# SPItoLVDS.net
KiCad netlist of a schematic drawn in Altium Designer
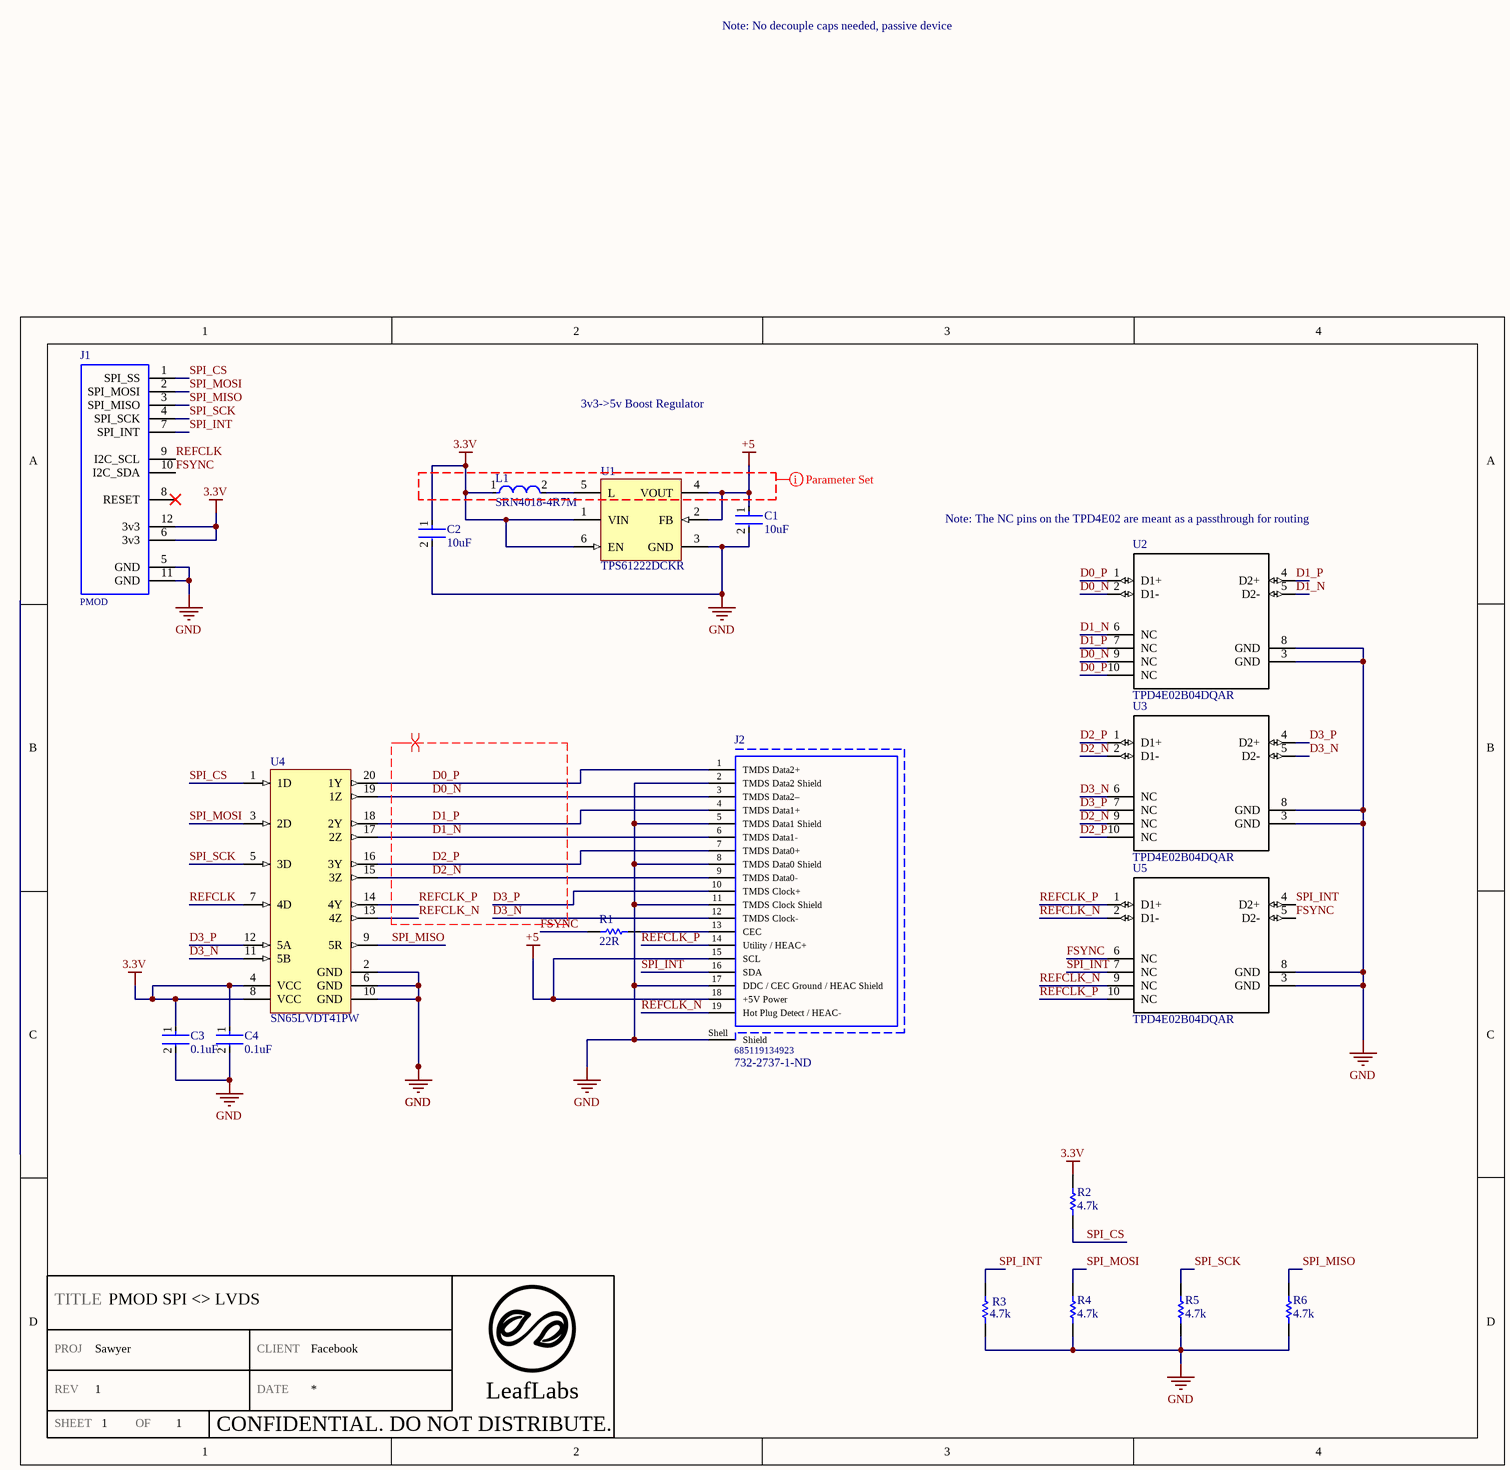
[diagram p0: SPItoLVDS.SchDoc]

(export (version "E")
  (design (tool "Eeschema 10.0.6"))
  (components
    (comp (ref "C1")
      (value "10uF")
      (footprint "FP-CC0603-DA-IPC_B")
      (description "CAP CER 10UF 0603")
      (libsource (lib "LeafLabs_Commercial") (part "CAP-0603-10uF"))
    )
    (comp (ref "C2")
      (value "10uF")
      (footprint "FP-CC0603-DA-IPC_B")
      (description "CAP CER 10UF 0603")
      (libsource (lib "LeafLabs_Commercial") (part "CAP-0603-10uF"))
    )
    (comp (ref "C3")
      (value "0.1uF")
      (footprint "FP-CC0603-DA-IPC_B")
      (description "CAP CER 0.1UF 16V X7R 0603")
      (fields
        (field (name "OCTOPART") "https://octopart.com/cc0603krx7r7bb104-yageo-192941")
        (field (name "TOLERANCE") "0.1")
      )
      (libsource (lib "LeafLabs_Commercial") (part "CAP-0603-0.1UF"))
    )
    (comp (ref "C4")
      (value "0.1uF")
      (footprint "FP-CC0603-DA-IPC_B")
      (description "CAP CER 0.1UF 16V X7R 0603")
      (fields
        (field (name "OCTOPART") "https://octopart.com/cc0603krx7r7bb104-yageo-192941")
        (field (name "TOLERANCE") "0.1")
      )
      (libsource (lib "LeafLabs_Commercial") (part "CAP-0603-0.1UF"))
    )
    (comp (ref "J1")
      (value "PMOD")
      (footprint "PMOD")
      (description "PMOD Connector, Through Hole, Standard pinout")
      (fields (field (name "PUBLISHER") "WurthElektronik"))
      (libsource (lib "LeafLabs_Commercial") (part "PMOD-TH"))
    )
    (comp (ref "J2")
      (value "685119134923")
      (footprint "685119134923")
      (description "HDMI Type A Receptacle WR-HDMI, Horizontal, SMT")
      (fields
        (field (name "MANUFACTURER") "Wurth Elektronik")
        (field (name "SUPPLIER PART NUMBER 1") "732-2737-1-ND")
        (field (name "PUBLISHER") "WurthElektronik")
      )
      (libsource (lib "LeafLabs_Commercial") (part "685119134923"))
    )
    (comp (ref "L1")
      (value "SRN4018-4R7M")
      (footprint "FP-SRN4018-MFG")
      (description "FIXED IND 4.7UH 1.9A 84 MOHM SMD")
      (fields
        (field (name "OCTOPART") "https://octopart.com/srn4018-4r7m-bourns-25452396")
        (field (name "TOLERANCE") "20%")
      )
      (libsource (lib "LeafLabs_Commercial") (part "SRN4018-4R7M"))
    )
    (comp (ref "R1")
      (value "22R")
      (footprint "RESC1609X50X30NL10T20")
      (description "Resistor 0603 22 Ohm")
      (libsource (lib "Resistors") (part "RES-0603-22R"))
    )
    (comp (ref "R2")
      (value "4.7k")
      (footprint "RESC1609X50X30NL10T20")
      (description "Resistor 0603 4.7k Ohm")
      (libsource (lib "LeafLabs_Commercial") (part "RES-0603-4.7k"))
    )
    (comp (ref "R3")
      (value "4.7k")
      (footprint "RESC1609X50X30NL10T20")
      (description "Resistor 0603 4.7k Ohm")
      (libsource (lib "LeafLabs_Commercial") (part "RES-0603-4.7k"))
    )
    (comp (ref "R4")
      (value "4.7k")
      (footprint "RESC1609X50X30NL10T20")
      (description "Resistor 0603 4.7k Ohm")
      (libsource (lib "LeafLabs_Commercial") (part "RES-0603-4.7k"))
    )
    (comp (ref "R5")
      (value "4.7k")
      (footprint "RESC1609X50X30NL10T20")
      (description "Resistor 0603 4.7k Ohm")
      (libsource (lib "LeafLabs_Commercial") (part "RES-0603-4.7k"))
    )
    (comp (ref "R6")
      (value "4.7k")
      (footprint "RESC1609X50X30NL10T20")
      (description "Resistor 0603 4.7k Ohm")
      (libsource (lib "LeafLabs_Commercial") (part "RES-0603-4.7k"))
    )
    (comp (ref "U1")
      (value "TPS61222DCKR")
      (footprint "SOT363_L")
      (fields (field (name "MANUFACTURER") "Texas Instruments"))
      (libsource (lib "LeafLabs_Commercial") (part "TPS61222DCKR"))
    )
    (comp (ref "U2")
      (value "TPD4E02B04DQAR")
      (footprint "DQA0010A")
      (description "4 Channel TVS Avalanch diode for USB3/HDMI2.0 protection")
      (fields
        (field (name "MANUFACTURER") "Texas Instruments")
        (field (name "COPYRIGHT") "Copyright (C) 2018 Accelerated Designs. All rights reserved")
      )
      (libsource (lib "LeafLabs_Commercial") (part "TPD4E02B04DQAR"))
    )
    (comp (ref "U3")
      (value "TPD4E02B04DQAR")
      (footprint "DQA0010A")
      (description "4 Channel TVS Avalanch diode for USB3/HDMI2.0 protection")
      (fields
        (field (name "MANUFACTURER") "Texas Instruments")
        (field (name "COPYRIGHT") "Copyright (C) 2018 Accelerated Designs. All rights reserved")
      )
      (libsource (lib "LeafLabs_Commercial") (part "TPD4E02B04DQAR"))
    )
    (comp (ref "U4")
      (value "SN65LVDT41PW")
      (footprint "PW0020A_L")
      (fields (field (name "MANUFACTURER") "Texas Instruments"))
      (libsource (lib "LeafLabs_Commercial") (part "SN65LVDT41PW"))
    )
    (comp (ref "U5")
      (value "TPD4E02B04DQAR")
      (footprint "DQA0010A")
      (description "4 Channel TVS Avalanch diode for USB3/HDMI2.0 protection")
      (fields
        (field (name "MANUFACTURER") "Texas Instruments")
        (field (name "COPYRIGHT") "Copyright (C) 2018 Accelerated Designs. All rights reserved")
      )
      (libsource (lib "LeafLabs_Commercial") (part "TPD4E02B04DQAR"))
    )
  )
  (nets
    (net (code "1") (name "+5") (class "Default")
      (node (ref "C1") (pin "1") (pinfunction "1_1") (pintype "passive"))
      (node (ref "J2") (pin "15") (pinfunction "SCL_15") (pintype "passive"))
      (node (ref "J2") (pin "18") (pinfunction "+5V_Power_18") (pintype "passive"))
      (node (ref "U1") (pin "2") (pinfunction "FB_2") (pintype "input"))
      (node (ref "U1") (pin "4") (pinfunction "VOUT_4") (pintype "power_in"))
    )
    (net (code "2") (name "/D0_N") (class "Default")
      (node (ref "J2") (pin "3") (pinfunction "TMDS_Data2–_3") (pintype "passive"))
      (node (ref "U2") (pin "2") (pinfunction "D1-_2") (pintype "bidirectional"))
      (node (ref "U2") (pin "9") (pinfunction "NC_9") (pintype "passive"))
      (node (ref "U4") (pin "19") (pinfunction "1Z_19") (pintype "output"))
    )
    (net (code "3") (name "/D0_P") (class "Default")
      (node (ref "J2") (pin "1") (pinfunction "TMDS_Data2+_1") (pintype "passive"))
      (node (ref "U2") (pin "1") (pinfunction "D1+_1") (pintype "bidirectional"))
      (node (ref "U2") (pin "10") (pinfunction "NC_10") (pintype "passive"))
      (node (ref "U4") (pin "20") (pinfunction "1Y_20") (pintype "output"))
    )
    (net (code "4") (name "/D1_N") (class "Default")
      (node (ref "J2") (pin "6") (pinfunction "TMDS_Data1-_6") (pintype "passive"))
      (node (ref "U2") (pin "5") (pinfunction "D2-_5") (pintype "bidirectional"))
      (node (ref "U2") (pin "6") (pinfunction "NC_6") (pintype "passive"))
      (node (ref "U4") (pin "17") (pinfunction "2Z_17") (pintype "output"))
    )
    (net (code "5") (name "/D1_P") (class "Default")
      (node (ref "J2") (pin "4") (pinfunction "TMDS_Data1+_4") (pintype "passive"))
      (node (ref "U2") (pin "4") (pinfunction "D2+_4") (pintype "bidirectional"))
      (node (ref "U2") (pin "7") (pinfunction "NC_7") (pintype "passive"))
      (node (ref "U4") (pin "18") (pinfunction "2Y_18") (pintype "output"))
    )
    (net (code "6") (name "/D2_N") (class "Default")
      (node (ref "J2") (pin "9") (pinfunction "TMDS_Data0-_9") (pintype "passive"))
      (node (ref "U3") (pin "2") (pinfunction "D1-_2") (pintype "bidirectional"))
      (node (ref "U3") (pin "9") (pinfunction "NC_9") (pintype "passive"))
      (node (ref "U4") (pin "15") (pinfunction "3Z_15") (pintype "output"))
    )
    (net (code "7") (name "/D2_P") (class "Default")
      (node (ref "J2") (pin "7") (pinfunction "TMDS_Data0+_7") (pintype "passive"))
      (node (ref "U3") (pin "1") (pinfunction "D1+_1") (pintype "bidirectional"))
      (node (ref "U3") (pin "10") (pinfunction "NC_10") (pintype "passive"))
      (node (ref "U4") (pin "16") (pinfunction "3Y_16") (pintype "output"))
    )
    (net (code "8") (name "/D3_N") (class "Default")
      (node (ref "J2") (pin "12") (pinfunction "TMDS_Clock-_12") (pintype "passive"))
      (node (ref "U3") (pin "5") (pinfunction "D2-_5") (pintype "bidirectional"))
      (node (ref "U3") (pin "6") (pinfunction "NC_6") (pintype "passive"))
      (node (ref "U4") (pin "11") (pinfunction "5B_11") (pintype "input"))
    )
    (net (code "9") (name "/D3_P") (class "Default")
      (node (ref "J2") (pin "10") (pinfunction "TMDS_Clock+_10") (pintype "passive"))
      (node (ref "U3") (pin "4") (pinfunction "D2+_4") (pintype "bidirectional"))
      (node (ref "U3") (pin "7") (pinfunction "NC_7") (pintype "passive"))
      (node (ref "U4") (pin "12") (pinfunction "5A_12") (pintype "input"))
    )
    (net (code "10") (name "/FSYNC") (class "Default")
      (node (ref "J1") (pin "10") (pinfunction "I2C_SDA_10") (pintype "passive"))
      (node (ref "R1") (pin "1") (pinfunction "1_1") (pintype "passive"))
      (node (ref "U5") (pin "5") (pinfunction "D2-_5") (pintype "bidirectional"))
      (node (ref "U5") (pin "6") (pinfunction "NC_6") (pintype "passive"))
    )
    (net (code "11") (name "/REFCLK") (class "Default")
      (node (ref "J1") (pin "9") (pinfunction "I2C_SCL_9") (pintype "passive"))
      (node (ref "U4") (pin "7") (pinfunction "4D_7") (pintype "input"))
    )
    (net (code "12") (name "/REFCLK_N") (class "Default")
      (node (ref "J2") (pin "19") (pinfunction "Hot_Plug_Detect_/_HEAC-_19") (pintype "passive"))
      (node (ref "U4") (pin "13") (pinfunction "4Z_13") (pintype "output"))
      (node (ref "U5") (pin "2") (pinfunction "D1-_2") (pintype "bidirectional"))
      (node (ref "U5") (pin "9") (pinfunction "NC_9") (pintype "passive"))
    )
    (net (code "13") (name "/REFCLK_P") (class "Default")
      (node (ref "J2") (pin "14") (pinfunction "Utility_/_HEAC+_14") (pintype "passive"))
      (node (ref "U4") (pin "14") (pinfunction "4Y_14") (pintype "output"))
      (node (ref "U5") (pin "1") (pinfunction "D1+_1") (pintype "bidirectional"))
      (node (ref "U5") (pin "10") (pinfunction "NC_10") (pintype "passive"))
    )
    (net (code "14") (name "/SPI_CS") (class "Default")
      (node (ref "J1") (pin "1") (pinfunction "SPI_SS_1") (pintype "passive"))
      (node (ref "R2") (pin "1") (pinfunction "1_1") (pintype "passive"))
      (node (ref "U4") (pin "1") (pinfunction "1D_1") (pintype "input"))
    )
    (net (code "15") (name "/SPI_INT") (class "Default")
      (node (ref "J1") (pin "7") (pinfunction "SPI_INT_7") (pintype "passive"))
      (node (ref "J2") (pin "16") (pinfunction "SDA_16") (pintype "passive"))
      (node (ref "R3") (pin "2") (pinfunction "2_2") (pintype "passive"))
      (node (ref "U5") (pin "4") (pinfunction "D2+_4") (pintype "bidirectional"))
      (node (ref "U5") (pin "7") (pinfunction "NC_7") (pintype "passive"))
    )
    (net (code "16") (name "/SPI_MISO") (class "Default")
      (node (ref "J1") (pin "3") (pinfunction "SPI_MISO_3") (pintype "passive"))
      (node (ref "R6") (pin "2") (pinfunction "2_2") (pintype "passive"))
      (node (ref "U4") (pin "9") (pinfunction "5R_9") (pintype "output"))
    )
    (net (code "17") (name "/SPI_MOSI") (class "Default")
      (node (ref "J1") (pin "2") (pinfunction "SPI_MOSI_2") (pintype "passive"))
      (node (ref "R4") (pin "2") (pinfunction "2_2") (pintype "passive"))
      (node (ref "U4") (pin "3") (pinfunction "2D_3") (pintype "input"))
    )
    (net (code "18") (name "/SPI_SCK") (class "Default")
      (node (ref "J1") (pin "4") (pinfunction "SPI_SCK_4") (pintype "passive"))
      (node (ref "R5") (pin "2") (pinfunction "2_2") (pintype "passive"))
      (node (ref "U4") (pin "5") (pinfunction "3D_5") (pintype "input"))
    )
    (net (code "19") (name "3.3V") (class "Default")
      (node (ref "C2") (pin "1") (pinfunction "1_1") (pintype "passive"))
      (node (ref "C3") (pin "1") (pinfunction "1_1") (pintype "passive"))
      (node (ref "C4") (pin "1") (pinfunction "1_1") (pintype "passive"))
      (node (ref "J1") (pin "12") (pinfunction "3v3_12") (pintype "power_in"))
      (node (ref "J1") (pin "6") (pinfunction "3v3_6") (pintype "power_in"))
      (node (ref "L1") (pin "1") (pinfunction "1_1") (pintype "passive"))
      (node (ref "R2") (pin "2") (pinfunction "2_2") (pintype "passive"))
      (node (ref "U1") (pin "1") (pinfunction "VIN_1") (pintype "power_in"))
      (node (ref "U1") (pin "6") (pinfunction "EN_6") (pintype "input"))
      (node (ref "U4") (pin "4") (pinfunction "VCC_4") (pintype "power_in"))
      (node (ref "U4") (pin "8") (pinfunction "VCC_8") (pintype "power_in"))
    )
    (net (code "20") (name "GND") (class "Default")
      (node (ref "C1") (pin "2") (pinfunction "2_2") (pintype "passive"))
      (node (ref "C2") (pin "2") (pinfunction "2_2") (pintype "passive"))
      (node (ref "C3") (pin "2") (pinfunction "2_2") (pintype "passive"))
      (node (ref "C4") (pin "2") (pinfunction "2_2") (pintype "passive"))
      (node (ref "J1") (pin "11") (pinfunction "GND_11") (pintype "passive"))
      (node (ref "J1") (pin "5") (pinfunction "GND_5") (pintype "passive"))
      (node (ref "J2") (pin "11") (pinfunction "TMDS_Clock_Shield_11") (pintype "passive"))
      (node (ref "J2") (pin "17") (pinfunction "DDC_/_CEC_Ground_/_HEAC_Shield_17") (pintype "passive"))
      (node (ref "J2") (pin "2") (pinfunction "TMDS_Data2_Shield_2") (pintype "passive"))
      (node (ref "J2") (pin "5") (pinfunction "TMDS_Data1_Shield_5") (pintype "passive"))
      (node (ref "J2") (pin "8") (pinfunction "TMDS_Data0_Shield_8") (pintype "passive"))
      (node (ref "J2") (pin "Shell") (pinfunction "Shield_Shell") (pintype "passive"))
      (node (ref "R3") (pin "1") (pinfunction "1_1") (pintype "passive"))
      (node (ref "R4") (pin "1") (pinfunction "1_1") (pintype "passive"))
      (node (ref "R5") (pin "1") (pinfunction "1_1") (pintype "passive"))
      (node (ref "R6") (pin "1") (pinfunction "1_1") (pintype "passive"))
      (node (ref "U1") (pin "3") (pinfunction "GND_3") (pintype "power_in"))
      (node (ref "U2") (pin "3") (pinfunction "GND_3") (pintype "power_in"))
      (node (ref "U2") (pin "8") (pinfunction "GND_8") (pintype "power_in"))
      (node (ref "U3") (pin "3") (pinfunction "GND_3") (pintype "power_in"))
      (node (ref "U3") (pin "8") (pinfunction "GND_8") (pintype "power_in"))
      (node (ref "U4") (pin "10") (pinfunction "GND_10") (pintype "power_in"))
      (node (ref "U4") (pin "2") (pinfunction "GND_2") (pintype "power_in"))
      (node (ref "U4") (pin "6") (pinfunction "GND_6") (pintype "power_in"))
      (node (ref "U5") (pin "3") (pinfunction "GND_3") (pintype "power_in"))
      (node (ref "U5") (pin "8") (pinfunction "GND_8") (pintype "power_in"))
    )
    (net (code "21") (name "Net-(J2-CEC)") (class "Default")
      (node (ref "J2") (pin "13") (pinfunction "CEC_13") (pintype "passive"))
      (node (ref "R1") (pin "2") (pinfunction "2_2") (pintype "passive"))
    )
    (net (code "22") (name "Net-(U1-L)") (class "Default")
      (node (ref "L1") (pin "2") (pinfunction "2_2") (pintype "passive"))
      (node (ref "U1") (pin "5") (pinfunction "L_5") (pintype "power_in"))
    )
    (net (code "23") (name "unconnected-(J1-RESET-Pad8)") (class "Default")
      (node (ref "J1") (pin "8") (pinfunction "RESET_8") (pintype "passive+no_connect"))
    )
  )
)
